# 11-SPI.net
KiCad netlist of a schematic drawn in Altium Designer
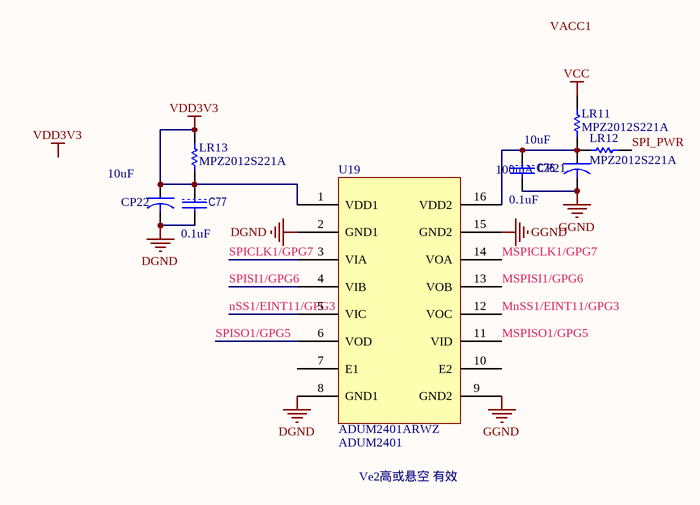
[diagram p0: 11-SPI.SchDoc]

(export (version "E")
  (design (tool "Eeschema 10.0.6"))
  (components
    (comp (ref "C76")
      (value "0.1uF")
      (footprint "1608[0603]C")
      (description "多层陶瓷电容器MLCC - SMD/SMT 0603 0.1uF 50volts X7R 10%")
      (fields (field (name "MANUFACTURER") "TDK") (field (name "MANUFACTURER PART NUMBER") "C1608X7R1H104K"))
      (libsource (lib "*") (part "CAP"))
    )
    (comp (ref "C77")
      (value "0.1uF")
      (footprint "1608[0603]C")
      (description "多层陶瓷电容器MLCC - SMD/SMT 0603 0.1uF 50volts X7R 10%")
      (fields (field (name "MANUFACTURER") "TDK") (field (name "MANUFACTURER PART NUMBER") "C1608X7R1H104K"))
      (libsource (lib "*") (part "CAP"))
    )
    (comp (ref "CP21")
      (value "10uF")
      (footprint "3216[1206]CB")
      (description "钽质电容器-固体SMD 16volts 10uF 10%")
      (fields (field (name "MANUFACTURER") "AVX") (field (name "MANUFACTURER PART NUMBER") "TAJA106K016RNJ"))
      (libsource (lib "*") (part "CAPACITOR"))
    )
    (comp (ref "CP22")
      (value "10uF")
      (footprint "3216[1206]CB")
      (description "钽质电容器-固体SMD 16volts 10uF 10%")
      (fields (field (name "MANUFACTURER") "AVX") (field (name "MANUFACTURER PART NUMBER") "TAJA106K016RNJ"))
      (libsource (lib "*") (part "CAPACITOR"))
    )
    (comp (ref "LR11")
      (value "MPZ2012S221A")
      (footprint "2012[0805]")
      (description "电磁干扰滤波珠子、扼流圈和阵列 Ferrite Chip Beads")
      (fields (field (name "MANUFACTURER") "TDK"))
      (libsource (lib "Miscellaneous Devices") (part "Res Semi"))
    )
    (comp (ref "LR12")
      (value "MPZ2012S221A")
      (footprint "2012[0805]")
      (description "电磁干扰滤波珠子、扼流圈和阵列 Ferrite Chip Beads")
      (fields (field (name "MANUFACTURER") "TDK"))
      (libsource (lib "Miscellaneous Devices") (part "Res Semi"))
    )
    (comp (ref "LR13")
      (value "MPZ2012S221A")
      (footprint "2012[0805]")
      (description "电磁干扰滤波珠子、扼流圈和阵列 Ferrite Chip Beads")
      (fields (field (name "MANUFACTURER") "TDK"))
      (libsource (lib "Miscellaneous Devices") (part "Res Semi"))
    )
    (comp (ref "U19")
      (value "ADUM2401ARWZ")
      (footprint "SOIC16W_N")
      (description "ADuM2401 1IN 3OUT")
      (fields (field (name "MANUFACTURER") "Analog Devices") (field (name "SERIES") "ADUM2401"))
      (libsource (lib "S3C2440V9") (part "ADuM2401"))
    )
  )
  (nets
    (net (code "1") (name "/MSPICLK1{slash}GPG7") (class "Default")
      (node (ref "U19") (pin "14") (pinfunction "VOA_14") (pintype "passive"))
    )
    (net (code "2") (name "/MSPISI1{slash}GPG6") (class "Default")
      (node (ref "U19") (pin "13") (pinfunction "VOB_13") (pintype "passive"))
    )
    (net (code "3") (name "/MSPISO1{slash}GPG5") (class "Default")
      (node (ref "U19") (pin "11") (pinfunction "VID_11") (pintype "passive"))
    )
    (net (code "4") (name "/MnSS1{slash}EINT11{slash}GPG3") (class "Default")
      (node (ref "U19") (pin "12") (pinfunction "VOC_12") (pintype "passive"))
    )
    (net (code "5") (name "/SPICLK1{slash}GPG7") (class "Default")
      (node (ref "U19") (pin "3") (pinfunction "VIA_3") (pintype "passive"))
    )
    (net (code "6") (name "/SPISI1{slash}GPG6") (class "Default")
      (node (ref "U19") (pin "4") (pinfunction "VIB_4") (pintype "passive"))
    )
    (net (code "7") (name "/SPISO1{slash}GPG5") (class "Default")
      (node (ref "U19") (pin "6") (pinfunction "VOD_6") (pintype "passive"))
    )
    (net (code "8") (name "/SPI_PWR") (class "Default")
      (node (ref "LR12") (pin "1") (pinfunction "1_1") (pintype "passive"))
    )
    (net (code "10") (name "/nSS1{slash}EINT11{slash}GPG3") (class "Default")
      (node (ref "U19") (pin "5") (pinfunction "VIC_5") (pintype "passive"))
    )
    (net (code "11") (name "DGND") (class "Default")
      (node (ref "C77") (pin "2") (pinfunction "2_2") (pintype "passive"))
      (node (ref "CP22") (pin "2") (pinfunction "2_2") (pintype "passive"))
      (node (ref "U19") (pin "2") (pinfunction "GND1_2") (pintype "passive"))
      (node (ref "U19") (pin "8") (pinfunction "GND1_8") (pintype "passive"))
    )
    (net (code "12") (name "GGND") (class "Default")
      (node (ref "C76") (pin "2") (pinfunction "2_2") (pintype "passive"))
      (node (ref "CP21") (pin "2") (pinfunction "2_2") (pintype "passive"))
      (node (ref "U19") (pin "15") (pinfunction "GND2_15") (pintype "passive"))
      (node (ref "U19") (pin "9") (pinfunction "GND2_9") (pintype "passive"))
    )
    (net (code "13") (name "Net-(U19-VDD2)") (class "Default")
      (node (ref "C76") (pin "1") (pinfunction "1_1") (pintype "passive"))
      (node (ref "CP21") (pin "1") (pinfunction "1_1") (pintype "passive"))
      (node (ref "LR11") (pin "1") (pinfunction "1_1") (pintype "passive"))
      (node (ref "LR12") (pin "2") (pinfunction "2_2") (pintype "passive"))
      (node (ref "U19") (pin "16") (pinfunction "VDD2_16") (pintype "passive"))
    )
    (net (code "14") (name "VCC") (class "Default")
      (node (ref "LR11") (pin "2") (pinfunction "2_2") (pintype "passive"))
    )
    (net (code "15") (name "VDD3V3") (class "Default")
      (node (ref "C77") (pin "1") (pinfunction "1_1") (pintype "passive"))
      (node (ref "CP22") (pin "1") (pinfunction "1_1") (pintype "passive"))
      (node (ref "LR13") (pin "1") (pinfunction "1_1") (pintype "passive"))
      (node (ref "LR13") (pin "2") (pinfunction "2_2") (pintype "passive"))
      (node (ref "U19") (pin "1") (pinfunction "VDD1_1") (pintype "passive"))
    )
    (net (code "16") (name "unconnected-(U19-E1-Pad7)") (class "Default")
      (node (ref "U19") (pin "7") (pinfunction "E1_7") (pintype "passive"))
    )
    (net (code "17") (name "unconnected-(U19-E2-Pad10)") (class "Default")
      (node (ref "U19") (pin "10") (pinfunction "E2_10") (pintype "passive"))
    )
  )
)
